# Sheet1.net
KiCad netlist of a schematic drawn in Altium Designer
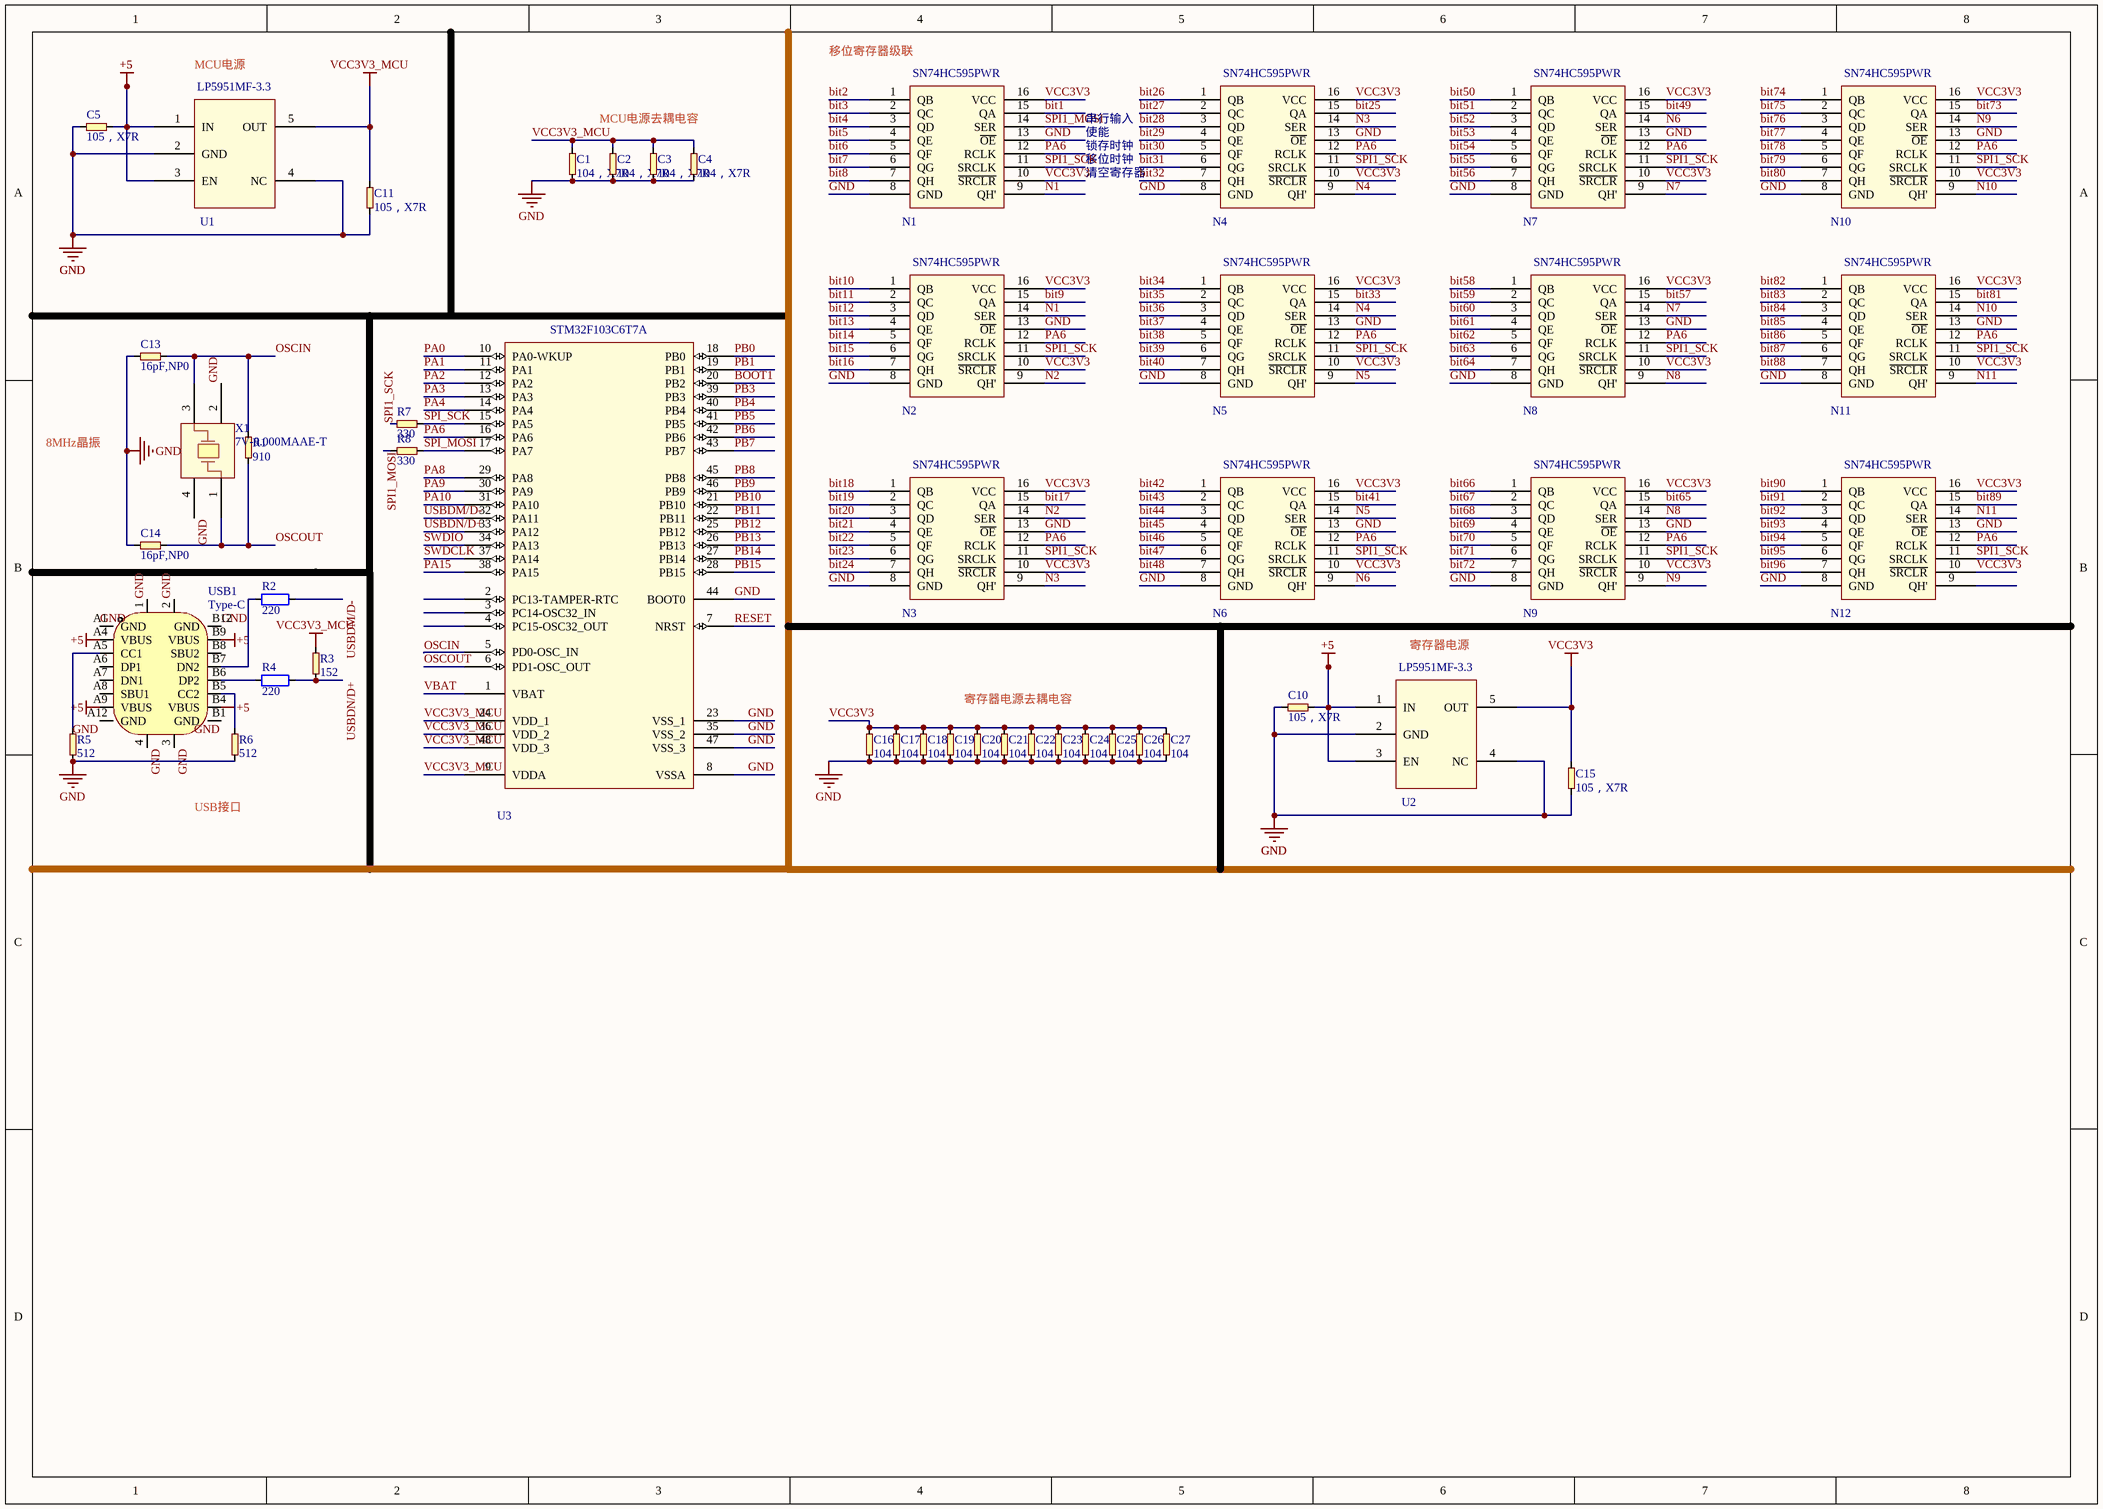
[diagram p0: Sheet1.SchDoc]

(export (version "E")
  (design (tool "Eeschema 10.0.6"))
  (components
    (comp (ref "C1") (value "104，X7R") (footprint "0603") (libsource (lib "原理图集成库") (part "0603电容")))
    (comp (ref "C2") (value "104，X7R") (footprint "0603") (libsource (lib "原理图集成库") (part "0603电容")))
    (comp (ref "C3") (value "104，X7R") (footprint "0603") (libsource (lib "原理图集成库") (part "0603电容")))
    (comp (ref "C4") (value "104，X7R") (footprint "0603") (libsource (lib "原理图集成库") (part "0603电容")))
    (comp (ref "C5") (value "105，X7R") (footprint "0603") (libsource (lib "") (part "0603电容_1")))
    (comp (ref "C10") (value "105，X7R") (footprint "0603") (libsource (lib "") (part "0603电容_1")))
    (comp (ref "C11") (value "105，X7R") (footprint "0603") (libsource (lib "原理图集成库") (part "0603电容")))
    (comp (ref "C13") (value "16pF,NP0") (footprint "0603") (libsource (lib "") (part "0603电容_1")))
    (comp (ref "C14") (value "16pF,NP0") (footprint "0603") (libsource (lib "") (part "0603电容_1")))
    (comp (ref "C15") (value "105，X7R") (footprint "0603") (libsource (lib "原理图集成库") (part "0603电容")))
    (comp (ref "C16") (value "104") (footprint "0603") (libsource (lib "原理图集成库") (part "0603电容")))
    (comp (ref "C17") (value "104") (footprint "0603") (libsource (lib "原理图集成库") (part "0603电容")))
    (comp (ref "C18") (value "104") (footprint "0603") (libsource (lib "原理图集成库") (part "0603电容")))
    (comp (ref "C19") (value "104") (footprint "0603") (libsource (lib "原理图集成库") (part "0603电容")))
    (comp (ref "C20") (value "104") (footprint "0603") (libsource (lib "原理图集成库") (part "0603电容")))
    (comp (ref "C21") (value "104") (footprint "0603") (libsource (lib "原理图集成库") (part "0603电容")))
    (comp (ref "C22") (value "104") (footprint "0603") (libsource (lib "原理图集成库") (part "0603电容")))
    (comp (ref "C23") (value "104") (footprint "0603") (libsource (lib "原理图集成库") (part "0603电容")))
    (comp (ref "C24") (value "104") (footprint "0603") (libsource (lib "原理图集成库") (part "0603电容")))
    (comp (ref "C25") (value "104") (footprint "0603") (libsource (lib "原理图集成库") (part "0603电容")))
    (comp (ref "C26") (value "104") (footprint "0603") (libsource (lib "原理图集成库") (part "0603电容")))
    (comp (ref "C27") (value "104") (footprint "0603") (libsource (lib "原理图集成库") (part "0603电容")))
    (comp (ref "N1")
      (value "SN74HC595PWR")
      (footprint "TSSOP16-0r65-5r0x4r4-H1r2:TSSOP16-0r65-5r0x4r4-H1r2")
      (libsource (lib "altium-import") (part "root_0_SN74HC595PWR_"))
    )
    (comp (ref "N2")
      (value "SN74HC595PWR")
      (footprint "TSSOP16-0r65-5r0x4r4-H1r2:TSSOP16-0r65-5r0x4r4-H1r2")
      (libsource (lib "altium-import") (part "root_0_SN74HC595PWR_"))
    )
    (comp (ref "N3")
      (value "SN74HC595PWR")
      (footprint "TSSOP16-0r65-5r0x4r4-H1r2:TSSOP16-0r65-5r0x4r4-H1r2")
      (libsource (lib "altium-import") (part "root_0_SN74HC595PWR_"))
    )
    (comp (ref "N4")
      (value "SN74HC595PWR")
      (footprint "TSSOP16-0r65-5r0x4r4-H1r2:TSSOP16-0r65-5r0x4r4-H1r2")
      (libsource (lib "altium-import") (part "root_0_SN74HC595PWR_"))
    )
    (comp (ref "N5")
      (value "SN74HC595PWR")
      (footprint "TSSOP16-0r65-5r0x4r4-H1r2:TSSOP16-0r65-5r0x4r4-H1r2")
      (libsource (lib "altium-import") (part "root_0_SN74HC595PWR_"))
    )
    (comp (ref "N6")
      (value "SN74HC595PWR")
      (footprint "TSSOP16-0r65-5r0x4r4-H1r2:TSSOP16-0r65-5r0x4r4-H1r2")
      (libsource (lib "altium-import") (part "root_0_SN74HC595PWR_"))
    )
    (comp (ref "N7")
      (value "SN74HC595PWR")
      (footprint "TSSOP16-0r65-5r0x4r4-H1r2:TSSOP16-0r65-5r0x4r4-H1r2")
      (libsource (lib "altium-import") (part "root_0_SN74HC595PWR_"))
    )
    (comp (ref "N8")
      (value "SN74HC595PWR")
      (footprint "TSSOP16-0r65-5r0x4r4-H1r2:TSSOP16-0r65-5r0x4r4-H1r2")
      (libsource (lib "altium-import") (part "root_0_SN74HC595PWR_"))
    )
    (comp (ref "N9")
      (value "SN74HC595PWR")
      (footprint "TSSOP16-0r65-5r0x4r4-H1r2:TSSOP16-0r65-5r0x4r4-H1r2")
      (libsource (lib "altium-import") (part "root_0_SN74HC595PWR_"))
    )
    (comp (ref "N10")
      (value "SN74HC595PWR")
      (footprint "TSSOP16-0r65-5r0x4r4-H1r2:TSSOP16-0r65-5r0x4r4-H1r2")
      (libsource (lib "altium-import") (part "root_0_SN74HC595PWR_"))
    )
    (comp (ref "N11")
      (value "SN74HC595PWR")
      (footprint "TSSOP16-0r65-5r0x4r4-H1r2:TSSOP16-0r65-5r0x4r4-H1r2")
      (libsource (lib "altium-import") (part "root_0_SN74HC595PWR_"))
    )
    (comp (ref "N12")
      (value "SN74HC595PWR")
      (footprint "TSSOP16-0r65-5r0x4r4-H1r2:TSSOP16-0r65-5r0x4r4-H1r2")
      (libsource (lib "altium-import") (part "root_0_SN74HC595PWR_"))
    )
    (comp (ref "R1") (value "910") (footprint "0603") (libsource (lib "") (part "0603电阻_1")))
    (comp (ref "R2")
      (value "220")
      (footprint "RES_0402")
      (description "Resistor_SMD")
      (libsource (lib "RC") (part "Resistor_SMD"))
    )
    (comp (ref "R3") (value "152") (footprint "0603") (libsource (lib "") (part "0603电阻_1")))
    (comp (ref "R4")
      (value "220")
      (footprint "RES_0402")
      (description "Resistor_SMD")
      (libsource (lib "RC") (part "Resistor_SMD"))
    )
    (comp (ref "R5") (value "512") (footprint "0603") (libsource (lib "") (part "0603电阻_1")))
    (comp (ref "R6") (value "512") (footprint "0603") (libsource (lib "") (part "0603电阻_1")))
    (comp (ref "R7") (value "330") (footprint "0603") (libsource (lib "原理图集成库") (part "0603电阻")))
    (comp (ref "R8") (value "330") (footprint "0603") (libsource (lib "原理图集成库") (part "0603电阻")))
    (comp (ref "U1")
      (value "LP5951MF-3.3")
      (footprint "SOT23-5_2r90x1r60-H1r18-P0r95_G:SOT23-5_2r90x1r60-H1r18-P0r95_G")
      (libsource (lib "altium-import") (part "root_0_LP5951MF-3.3_"))
    )
    (comp (ref "U2")
      (value "LP5951MF-3.3")
      (footprint "SOT23-5_2r90x1r60-H1r18-P0r95_G:SOT23-5_2r90x1r60-H1r18-P0r95_G")
      (libsource (lib "altium-import") (part "root_0_LP5951MF-3.3_"))
    )
    (comp (ref "U3")
      (value "STM32F103C6T7A")
      (footprint "LQFP48-0r5-7x7-H1r6:LQFP48-0r5-7x7-H1r6")
      (libsource (lib "altium-import") (part "root_0_STM32F103C6T7A_"))
    )
    (comp (ref "USB1")
      (value "Type-C")
      (footprint "TYPE-C_16P")
      (description "USB-Type-C_16P")
      (libsource (lib "Connector") (part "USB-Type-C"))
    )
    (comp (ref "X1")
      (value "7V-8.000MAAE-T")
      (footprint "RESO3225-4_3r20x2r50-H0r90-P2r10:RESO3225-4_3r20x2r50-H0r90-P2r10")
      (libsource (lib "altium-import") (part "root_1_7V-8.000MAAE-T_"))
    )
  )
  (nets
    (net (code "1") (name "+5") (class "Default")
      (node (ref "C10") (pin "2") (pinfunction "2_2") (pintype "passive"))
      (node (ref "C5") (pin "2") (pinfunction "2_2") (pintype "passive"))
      (node (ref "U1") (pin "1") (pinfunction "IN_1") (pintype "passive"))
      (node (ref "U1") (pin "3") (pinfunction "EN_3") (pintype "passive"))
      (node (ref "U2") (pin "1") (pinfunction "IN_1") (pintype "passive"))
      (node (ref "U2") (pin "3") (pinfunction "EN_3") (pintype "passive"))
      (node (ref "USB1") (pin "A4") (pinfunction "VBUS_A4") (pintype "passive"))
      (node (ref "USB1") (pin "A9") (pinfunction "VBUS_A9") (pintype "passive"))
      (node (ref "USB1") (pin "B4") (pinfunction "VBUS_B4") (pintype "passive"))
      (node (ref "USB1") (pin "B9") (pinfunction "VBUS_B9") (pintype "passive"))
    )
    (net (code "2") (name "/BOOT1") (class "Default")
      (node (ref "U3") (pin "20") (pinfunction "PB2_20") (pintype "bidirectional"))
    )
    (net (code "3") (name "/N1") (class "Default")
      (node (ref "N1") (pin "9") (pinfunction "QH'_9") (pintype "passive"))
      (node (ref "N2") (pin "14") (pinfunction "SER_14") (pintype "passive"))
    )
    (net (code "4") (name "/N2") (class "Default")
      (node (ref "N2") (pin "9") (pinfunction "QH'_9") (pintype "passive"))
      (node (ref "N3") (pin "14") (pinfunction "SER_14") (pintype "passive"))
    )
    (net (code "5") (name "/N3") (class "Default")
      (node (ref "N3") (pin "9") (pinfunction "QH'_9") (pintype "passive"))
      (node (ref "N4") (pin "14") (pinfunction "SER_14") (pintype "passive"))
    )
    (net (code "6") (name "/N4") (class "Default")
      (node (ref "N4") (pin "9") (pinfunction "QH'_9") (pintype "passive"))
      (node (ref "N5") (pin "14") (pinfunction "SER_14") (pintype "passive"))
    )
    (net (code "7") (name "/N5") (class "Default")
      (node (ref "N5") (pin "9") (pinfunction "QH'_9") (pintype "passive"))
      (node (ref "N6") (pin "14") (pinfunction "SER_14") (pintype "passive"))
    )
    (net (code "8") (name "/N6") (class "Default")
      (node (ref "N6") (pin "9") (pinfunction "QH'_9") (pintype "passive"))
      (node (ref "N7") (pin "14") (pinfunction "SER_14") (pintype "passive"))
    )
    (net (code "9") (name "/N7") (class "Default")
      (node (ref "N7") (pin "9") (pinfunction "QH'_9") (pintype "passive"))
      (node (ref "N8") (pin "14") (pinfunction "SER_14") (pintype "passive"))
    )
    (net (code "10") (name "/N8") (class "Default")
      (node (ref "N8") (pin "9") (pinfunction "QH'_9") (pintype "passive"))
      (node (ref "N9") (pin "14") (pinfunction "SER_14") (pintype "passive"))
    )
    (net (code "11") (name "/N9") (class "Default")
      (node (ref "N10") (pin "14") (pinfunction "SER_14") (pintype "passive"))
      (node (ref "N9") (pin "9") (pinfunction "QH'_9") (pintype "passive"))
    )
    (net (code "12") (name "/N10") (class "Default")
      (node (ref "N10") (pin "9") (pinfunction "QH'_9") (pintype "passive"))
      (node (ref "N11") (pin "14") (pinfunction "SER_14") (pintype "passive"))
    )
    (net (code "13") (name "/N11") (class "Default")
      (node (ref "N11") (pin "9") (pinfunction "QH'_9") (pintype "passive"))
      (node (ref "N12") (pin "14") (pinfunction "SER_14") (pintype "passive"))
    )
    (net (code "14") (name "/OSCIN") (class "Default")
      (node (ref "C13") (pin "2") (pinfunction "2_2") (pintype "passive"))
      (node (ref "R1") (pin "2") (pinfunction "2_2") (pintype "passive"))
      (node (ref "U3") (pin "5") (pinfunction "PD0-OSC_IN_5") (pintype "bidirectional"))
      (node (ref "X1") (pin "3") (pinfunction "3_3") (pintype "passive"))
    )
    (net (code "15") (name "/OSCOUT") (class "Default")
      (node (ref "C14") (pin "2") (pinfunction "2_2") (pintype "passive"))
      (node (ref "R1") (pin "1") (pinfunction "1_1") (pintype "passive"))
      (node (ref "U3") (pin "6") (pinfunction "PD1-OSC_OUT_6") (pintype "bidirectional"))
      (node (ref "X1") (pin "1") (pinfunction "1_1") (pintype "passive"))
    )
    (net (code "16") (name "/PA0") (class "Default")
      (node (ref "U3") (pin "10") (pinfunction "PA0-WKUP_10") (pintype "bidirectional"))
    )
    (net (code "17") (name "/PA1") (class "Default")
      (node (ref "U3") (pin "11") (pinfunction "PA1_11") (pintype "bidirectional"))
    )
    (net (code "18") (name "/PA2") (class "Default")
      (node (ref "U3") (pin "12") (pinfunction "PA2_12") (pintype "bidirectional"))
    )
    (net (code "19") (name "/PA3") (class "Default")
      (node (ref "U3") (pin "13") (pinfunction "PA3_13") (pintype "bidirectional"))
    )
    (net (code "20") (name "/PA4") (class "Default")
      (node (ref "U3") (pin "14") (pinfunction "PA4_14") (pintype "bidirectional"))
    )
    (net (code "21") (name "/PA6") (class "Default")
      (node (ref "N1") (pin "12") (pinfunction "RCLK_12") (pintype "passive"))
      (node (ref "N10") (pin "12") (pinfunction "RCLK_12") (pintype "passive"))
      (node (ref "N11") (pin "12") (pinfunction "RCLK_12") (pintype "passive"))
      (node (ref "N12") (pin "12") (pinfunction "RCLK_12") (pintype "passive"))
      (node (ref "N2") (pin "12") (pinfunction "RCLK_12") (pintype "passive"))
      (node (ref "N3") (pin "12") (pinfunction "RCLK_12") (pintype "passive"))
      (node (ref "N4") (pin "12") (pinfunction "RCLK_12") (pintype "passive"))
      (node (ref "N5") (pin "12") (pinfunction "RCLK_12") (pintype "passive"))
      (node (ref "N6") (pin "12") (pinfunction "RCLK_12") (pintype "passive"))
      (node (ref "N7") (pin "12") (pinfunction "RCLK_12") (pintype "passive"))
      (node (ref "N8") (pin "12") (pinfunction "RCLK_12") (pintype "passive"))
      (node (ref "N9") (pin "12") (pinfunction "RCLK_12") (pintype "passive"))
      (node (ref "U3") (pin "16") (pinfunction "PA6_16") (pintype "bidirectional"))
    )
    (net (code "22") (name "/PA8") (class "Default")
      (node (ref "U3") (pin "29") (pinfunction "PA8_29") (pintype "bidirectional"))
    )
    (net (code "23") (name "/PA9") (class "Default")
      (node (ref "U3") (pin "30") (pinfunction "PA9_30") (pintype "bidirectional"))
    )
    (net (code "24") (name "/PA10") (class "Default")
      (node (ref "U3") (pin "31") (pinfunction "PA10_31") (pintype "bidirectional"))
    )
    (net (code "25") (name "/PA15") (class "Default")
      (node (ref "U3") (pin "38") (pinfunction "PA15_38") (pintype "bidirectional"))
    )
    (net (code "26") (name "/PB0") (class "Default")
      (node (ref "U3") (pin "18") (pinfunction "PB0_18") (pintype "bidirectional"))
    )
    (net (code "27") (name "/PB1") (class "Default")
      (node (ref "U3") (pin "19") (pinfunction "PB1_19") (pintype "bidirectional"))
    )
    (net (code "28") (name "/PB3") (class "Default")
      (node (ref "U3") (pin "39") (pinfunction "PB3_39") (pintype "bidirectional"))
    )
    (net (code "29") (name "/PB4") (class "Default")
      (node (ref "U3") (pin "40") (pinfunction "PB4_40") (pintype "bidirectional"))
    )
    (net (code "30") (name "/PB5") (class "Default")
      (node (ref "U3") (pin "41") (pinfunction "PB5_41") (pintype "bidirectional"))
    )
    (net (code "31") (name "/PB6") (class "Default")
      (node (ref "U3") (pin "42") (pinfunction "PB6_42") (pintype "bidirectional"))
    )
    (net (code "32") (name "/PB7") (class "Default")
      (node (ref "U3") (pin "43") (pinfunction "PB7_43") (pintype "bidirectional"))
    )
    (net (code "33") (name "/PB8") (class "Default")
      (node (ref "U3") (pin "45") (pinfunction "PB8_45") (pintype "bidirectional"))
    )
    (net (code "34") (name "/PB9") (class "Default")
      (node (ref "U3") (pin "46") (pinfunction "PB9_46") (pintype "bidirectional"))
    )
    (net (code "35") (name "/PB10") (class "Default")
      (node (ref "U3") (pin "21") (pinfunction "PB10_21") (pintype "bidirectional"))
    )
    (net (code "36") (name "/PB11") (class "Default")
      (node (ref "U3") (pin "22") (pinfunction "PB11_22") (pintype "bidirectional"))
    )
    (net (code "37") (name "/PB12") (class "Default")
      (node (ref "U3") (pin "25") (pinfunction "PB12_25") (pintype "bidirectional"))
    )
    (net (code "38") (name "/PB13") (class "Default")
      (node (ref "U3") (pin "26") (pinfunction "PB13_26") (pintype "bidirectional"))
    )
    (net (code "39") (name "/PB14") (class "Default")
      (node (ref "U3") (pin "27") (pinfunction "PB14_27") (pintype "bidirectional"))
    )
    (net (code "40") (name "/PB15") (class "Default")
      (node (ref "U3") (pin "28") (pinfunction "PB15_28") (pintype "bidirectional"))
    )
    (net (code "41") (name "/RESET") (class "Default")
      (node (ref "U3") (pin "7") (pinfunction "NRST_7") (pintype "bidirectional"))
    )
    (net (code "42") (name "/SPI1_MOSI") (class "Default")
      (node (ref "N1") (pin "14") (pinfunction "SER_14") (pintype "passive"))
      (node (ref "R8") (pin "1") (pinfunction "1_1") (pintype "passive"))
    )
    (net (code "43") (name "/SPI1_SCK") (class "Default")
      (node (ref "N1") (pin "11") (pinfunction "SRCLK_11") (pintype "passive"))
      (node (ref "N10") (pin "11") (pinfunction "SRCLK_11") (pintype "passive"))
      (node (ref "N11") (pin "11") (pinfunction "SRCLK_11") (pintype "passive"))
      (node (ref "N12") (pin "11") (pinfunction "SRCLK_11") (pintype "passive"))
      (node (ref "N2") (pin "11") (pinfunction "SRCLK_11") (pintype "passive"))
      (node (ref "N3") (pin "11") (pinfunction "SRCLK_11") (pintype "passive"))
      (node (ref "N4") (pin "11") (pinfunction "SRCLK_11") (pintype "passive"))
      (node (ref "N5") (pin "11") (pinfunction "SRCLK_11") (pintype "passive"))
      (node (ref "N6") (pin "11") (pinfunction "SRCLK_11") (pintype "passive"))
      (node (ref "N7") (pin "11") (pinfunction "SRCLK_11") (pintype "passive"))
      (node (ref "N8") (pin "11") (pinfunction "SRCLK_11") (pintype "passive"))
      (node (ref "N9") (pin "11") (pinfunction "SRCLK_11") (pintype "passive"))
      (node (ref "R7") (pin "1") (pinfunction "1_1") (pintype "passive"))
    )
    (net (code "44") (name "/SPI_MOSI") (class "Default")
      (node (ref "R8") (pin "2") (pinfunction "2_2") (pintype "passive"))
      (node (ref "U3") (pin "17") (pinfunction "PA7_17") (pintype "bidirectional"))
    )
    (net (code "45") (name "/SPI_SCK") (class "Default")
      (node (ref "R7") (pin "2") (pinfunction "2_2") (pintype "passive"))
      (node (ref "U3") (pin "15") (pinfunction "PA5_15") (pintype "bidirectional"))
    )
    (net (code "46") (name "/SWDCLK") (class "Default")
      (node (ref "U3") (pin "37") (pinfunction "PA14_37") (pintype "bidirectional"))
    )
    (net (code "47") (name "/SWDIO") (class "Default")
      (node (ref "U3") (pin "34") (pinfunction "PA13_34") (pintype "bidirectional"))
    )
    (net (code "48") (name "/USBDM{slash}D-") (class "Default")
      (node (ref "R2") (pin "2") (pinfunction "2_2") (pintype "passive"))
      (node (ref "U3") (pin "32") (pinfunction "PA11_32") (pintype "bidirectional"))
    )
    (net (code "49") (name "/USBDN{slash}D+") (class "Default")
      (node (ref "R3") (pin "1") (pinfunction "1_1") (pintype "passive"))
      (node (ref "R4") (pin "2") (pinfunction "2_2") (pintype "passive"))
      (node (ref "U3") (pin "33") (pinfunction "PA12_33") (pintype "bidirectional"))
    )
    (net (code "50") (name "/VBAT") (class "Default")
      (node (ref "U3") (pin "1") (pinfunction "VBAT_1") (pintype "power_in"))
    )
    (net (code "51") (name "/bit1") (class "Default")
      (node (ref "N1") (pin "15") (pinfunction "QA_15") (pintype "passive"))
    )
    (net (code "52") (name "/bit2") (class "Default")
      (node (ref "N1") (pin "1") (pinfunction "QB_1") (pintype "passive"))
    )
    (net (code "53") (name "/bit3") (class "Default")
      (node (ref "N1") (pin "2") (pinfunction "QC_2") (pintype "passive"))
    )
    (net (code "54") (name "/bit4") (class "Default")
      (node (ref "N1") (pin "3") (pinfunction "QD_3") (pintype "passive"))
    )
    (net (code "55") (name "/bit5") (class "Default")
      (node (ref "N1") (pin "4") (pinfunction "QE_4") (pintype "passive"))
    )
    (net (code "56") (name "/bit6") (class "Default")
      (node (ref "N1") (pin "5") (pinfunction "QF_5") (pintype "passive"))
    )
    (net (code "57") (name "/bit7") (class "Default")
      (node (ref "N1") (pin "6") (pinfunction "QG_6") (pintype "passive"))
    )
    (net (code "58") (name "/bit8") (class "Default")
      (node (ref "N1") (pin "7") (pinfunction "QH_7") (pintype "passive"))
    )
    (net (code "59") (name "/bit9") (class "Default")
      (node (ref "N2") (pin "15") (pinfunction "QA_15") (pintype "passive"))
    )
    (net (code "60") (name "/bit10") (class "Default")
      (node (ref "N2") (pin "1") (pinfunction "QB_1") (pintype "passive"))
    )
    (net (code "61") (name "/bit11") (class "Default")
      (node (ref "N2") (pin "2") (pinfunction "QC_2") (pintype "passive"))
    )
    (net (code "62") (name "/bit12") (class "Default")
      (node (ref "N2") (pin "3") (pinfunction "QD_3") (pintype "passive"))
    )
    (net (code "63") (name "/bit13") (class "Default")
      (node (ref "N2") (pin "4") (pinfunction "QE_4") (pintype "passive"))
    )
    (net (code "64") (name "/bit14") (class "Default")
      (node (ref "N2") (pin "5") (pinfunction "QF_5") (pintype "passive"))
    )
    (net (code "65") (name "/bit15") (class "Default")
      (node (ref "N2") (pin "6") (pinfunction "QG_6") (pintype "passive"))
    )
    (net (code "66") (name "/bit16") (class "Default")
      (node (ref "N2") (pin "7") (pinfunction "QH_7") (pintype "passive"))
    )
    (net (code "67") (name "/bit17") (class "Default")
      (node (ref "N3") (pin "15") (pinfunction "QA_15") (pintype "passive"))
    )
    (net (code "68") (name "/bit18") (class "Default")
      (node (ref "N3") (pin "1") (pinfunction "QB_1") (pintype "passive"))
    )
    (net (code "69") (name "/bit19") (class "Default")
      (node (ref "N3") (pin "2") (pinfunction "QC_2") (pintype "passive"))
    )
    (net (code "70") (name "/bit20") (class "Default")
      (node (ref "N3") (pin "3") (pinfunction "QD_3") (pintype "passive"))
    )
    (net (code "71") (name "/bit21") (class "Default")
      (node (ref "N3") (pin "4") (pinfunction "QE_4") (pintype "passive"))
    )
    (net (code "72") (name "/bit22") (class "Default")
      (node (ref "N3") (pin "5") (pinfunction "QF_5") (pintype "passive"))
    )
    (net (code "73") (name "/bit23") (class "Default")
      (node (ref "N3") (pin "6") (pinfunction "QG_6") (pintype "passive"))
    )
    (net (code "74") (name "/bit24") (class "Default")
      (node (ref "N3") (pin "7") (pinfunction "QH_7") (pintype "passive"))
    )
    (net (code "75") (name "/bit25") (class "Default")
      (node (ref "N4") (pin "15") (pinfunction "QA_15") (pintype "passive"))
    )
    (net (code "76") (name "/bit26") (class "Default")
      (node (ref "N4") (pin "1") (pinfunction "QB_1") (pintype "passive"))
    )
    (net (code "77") (name "/bit27") (class "Default")
      (node (ref "N4") (pin "2") (pinfunction "QC_2") (pintype "passive"))
    )
    (net (code "78") (name "/bit28") (class "Default")
      (node (ref "N4") (pin "3") (pinfunction "QD_3") (pintype "passive"))
    )
    (net (code "79") (name "/bit29") (class "Default")
      (node (ref "N4") (pin "4") (pinfunction "QE_4") (pintype "passive"))
    )
    (net (code "80") (name "/bit30") (class "Default")
      (node (ref "N4") (pin "5") (pinfunction "QF_5") (pintype "passive"))
    )
    (net (code "81") (name "/bit31") (class "Default")
      (node (ref "N4") (pin "6") (pinfunction "QG_6") (pintype "passive"))
    )
    (net (code "82") (name "/bit32") (class "Default")
      (node (ref "N4") (pin "7") (pinfunction "QH_7") (pintype "passive"))
    )
    (net (code "83") (name "/bit33") (class "Default")
      (node (ref "N5") (pin "15") (pinfunction "QA_15") (pintype "passive"))
    )
    (net (code "84") (name "/bit34") (class "Default")
      (node (ref "N5") (pin "1") (pinfunction "QB_1") (pintype "passive"))
    )
    (net (code "85") (name "/bit35") (class "Default")
      (node (ref "N5") (pin "2") (pinfunction "QC_2") (pintype "passive"))
    )
    (net (code "86") (name "/bit36") (class "Default")
      (node (ref "N5") (pin "3") (pinfunction "QD_3") (pintype "passive"))
    )
    (net (code "87") (name "/bit37") (class "Default")
      (node (ref "N5") (pin "4") (pinfunction "QE_4") (pintype "passive"))
    )
    (net (code "88") (name "/bit38") (class "Default")
      (node (ref "N5") (pin "5") (pinfunction "QF_5") (pintype "passive"))
    )
    (net (code "89") (name "/bit39") (class "Default")
      (node (ref "N5") (pin "6") (pinfunction "QG_6") (pintype "passive"))
    )
    (net (code "90") (name "/bit40") (class "Default")
      (node (ref "N5") (pin "7") (pinfunction "QH_7") (pintype "passive"))
    )
    (net (code "91") (name "/bit41") (class "Default")
      (node (ref "N6") (pin "15") (pinfunction "QA_15") (pintype "passive"))
    )
    (net (code "92") (name "/bit42") (class "Default")
      (node (ref "N6") (pin "1") (pinfunction "QB_1") (pintype "passive"))
    )
    (net (code "93") (name "/bit43") (class "Default")
      (node (ref "N6") (pin "2") (pinfunction "QC_2") (pintype "passive"))
    )
    (net (code "94") (name "/bit44") (class "Default")
      (node (ref "N6") (pin "3") (pinfunction "QD_3") (pintype "passive"))
    )
    (net (code "95") (name "/bit45") (class "Default")
      (node (ref "N6") (pin "4") (pinfunction "QE_4") (pintype "passive"))
    )
    (net (code "96") (name "/bit46") (class "Default")
      (node (ref "N6") (pin "5") (pinfunction "QF_5") (pintype "passive"))
    )
    (net (code "97") (name "/bit47") (class "Default")
      (node (ref "N6") (pin "6") (pinfunction "QG_6") (pintype "passive"))
    )
    (net (code "98") (name "/bit48") (class "Default")
      (node (ref "N6") (pin "7") (pinfunction "QH_7") (pintype "passive"))
    )
    (net (code "99") (name "/bit49") (class "Default")
      (node (ref "N7") (pin "15") (pinfunction "QA_15") (pintype "passive"))
    )
    (net (code "100") (name "/bit50") (class "Default")
      (node (ref "N7") (pin "1") (pinfunction "QB_1") (pintype "passive"))
    )
    (net (code "101") (name "/bit51") (class "Default")
      (node (ref "N7") (pin "2") (pinfunction "QC_2") (pintype "passive"))
    )
    (net (code "102") (name "/bit52") (class "Default")
      (node (ref "N7") (pin "3") (pinfunction "QD_3") (pintype "passive"))
    )
    (net (code "103") (name "/bit53") (class "Default")
      (node (ref "N7") (pin "4") (pinfunction "QE_4") (pintype "passive"))
    )
    (net (code "104") (name "/bit54") (class "Default")
      (node (ref "N7") (pin "5") (pinfunction "QF_5") (pintype "passive"))
    )
    (net (code "105") (name "/bit55") (class "Default")
      (node (ref "N7") (pin "6") (pinfunction "QG_6") (pintype "passive"))
    )
    (net (code "106") (name "/bit56") (class "Default")
      (node (ref "N7") (pin "7") (pinfunction "QH_7") (pintype "passive"))
    )
    (net (code "107") (name "/bit57") (class "Default")
      (node (ref "N8") (pin "15") (pinfunction "QA_15") (pintype "passive"))
    )
    (net (code "108") (name "/bit58") (class "Default")
      (node (ref "N8") (pin "1") (pinfunction "QB_1") (pintype "passive"))
    )
    (net (code "109") (name "/bit59") (class "Default")
      (node (ref "N8") (pin "2") (pinfunction "QC_2") (pintype "passive"))
    )
    (net (code "110") (name "/bit60") (class "Default")
      (node (ref "N8") (pin "3") (pinfunction "QD_3") (pintype "passive"))
    )
    (net (code "111") (name "/bit61") (class "Default")
      (node (ref "N8") (pin "4") (pinfunction "QE_4") (pintype "passive"))
    )
    (net (code "112") (name "/bit62") (class "Default")
      (node (ref "N8") (pin "5") (pinfunction "QF_5") (pintype "passive"))
    )
    (net (code "113") (name "/bit63") (class "Default")
      (node (ref "N8") (pin "6") (pinfunction "QG_6") (pintype "passive"))
    )
    (net (code "114") (name "/bit64") (class "Default")
      (node (ref "N8") (pin "7") (pinfunction "QH_7") (pintype "passive"))
    )
    (net (code "115") (name "/bit65") (class "Default")
      (node (ref "N9") (pin "15") (pinfunction "QA_15") (pintype "passive"))
    )
    (net (code "116") (name "/bit66") (class "Default")
      (node (ref "N9") (pin "1") (pinfunction "QB_1") (pintype "passive"))
    )
    (net (code "117") (name "/bit67") (class "Default")
      (node (ref "N9") (pin "2") (pinfunction "QC_2") (pintype "passive"))
    )
    (net (code "118") (name "/bit68") (class "Default")
      (node (ref "N9") (pin "3") (pinfunction "QD_3") (pintype "passive"))
    )
    (net (code "119") (name "/bit69") (class "Default")
      (node (ref "N9") (pin "4") (pinfunction "QE_4") (pintype "passive"))
    )
    (net (code "120") (name "/bit70") (class "Default")
      (node (ref "N9") (pin "5") (pinfunction "QF_5") (pintype "passive"))
    )
    (net (code "121") (name "/bit71") (class "Default")
      (node (ref "N9") (pin "6") (pinfunction "QG_6") (pintype "passive"))
    )
    (net (code "122") (name "/bit72") (class "Default")
      (node (ref "N9") (pin "7") (pinfunction "QH_7") (pintype "passive"))
    )
    (net (code "123") (name "/bit73") (class "Default")
      (node (ref "N10") (pin "15") (pinfunction "QA_15") (pintype "passive"))
    )
    (net (code "124") (name "/bit74") (class "Default")
      (node (ref "N10") (pin "1") (pinfunction "QB_1") (pintype "passive"))
    )
    (net (code "125") (name "/bit75") (class "Default")
      (node (ref "N10") (pin "2") (pinfunction "QC_2") (pintype "passive"))
    )
    (net (code "126") (name "/bit76") (class "Default")
      (node (ref "N10") (pin "3") (pinfunction "QD_3") (pintype "passive"))
    )
    (net (code "127") (name "/bit77") (class "Default")
      (node (ref "N10") (pin "4") (pinfunction "QE_4") (pintype "passive"))
    )
    (net (code "128") (name "/bit78") (class "Default")
      (node (ref "N10") (pin "5") (pinfunction "QF_5") (pintype "passive"))
    )
    (net (code "129") (name "/bit79") (class "Default")
      (node (ref "N10") (pin "6") (pinfunction "QG_6") (pintype "passive"))
    )
    (net (code "130") (name "/bit80") (class "Default")
      (node (ref "N10") (pin "7") (pinfunction "QH_7") (pintype "passive"))
    )
    (net (code "131") (name "/bit81") (class "Default")
      (node (ref "N11") (pin "15") (pinfunction "QA_15") (pintype "passive"))
    )
    (net (code "132") (name "/bit82") (class "Default")
      (node (ref "N11") (pin "1") (pinfunction "QB_1") (pintype "passive"))
    )
    (net (code "133") (name "/bit83") (class "Default")
      (node (ref "N11") (pin "2") (pinfunction "QC_2") (pintype "passive"))
    )
    (net (code "134") (name "/bit84") (class "Default")
      (node (ref "N11") (pin "3") (pinfunction "QD_3") (pintype "passive"))
    )
    (net (code "135") (name "/bit85") (class "Default")
      (node (ref "N11") (pin "4") (pinfunction "QE_4") (pintype "passive"))
    )
    (net (code "136") (name "/bit86") (class "Default")
      (node (ref "N11") (pin "5") (pinfunction "QF_5") (pintype "passive"))
    )
    (net (code "137") (name "/bit87") (class "Default")
      (node (ref "N11") (pin "6") (pinfunction "QG_6") (pintype "passive"))
    )
    (net (code "138") (name "/bit88") (class "Default")
      (node (ref "N11") (pin "7") (pinfunction "QH_7") (pintype "passive"))
    )
    (net (code "139") (name "/bit89") (class "Default")
      (node (ref "N12") (pin "15") (pinfunction "QA_15") (pintype "passive"))
    )
    (net (code "140") (name "/bit90") (class "Default")
      (node (ref "N12") (pin "1") (pinfunction "QB_1") (pintype "passive"))
    )
    (net (code "141") (name "/bit91") (class "Default")
      (node (ref "N12") (pin "2") (pinfunction "QC_2") (pintype "passive"))
    )
    (net (code "142") (name "/bit92") (class "Default")
      (node (ref "N12") (pin "3") (pinfunction "QD_3") (pintype "passive"))
    )
    (net (code "143") (name "/bit93") (class "Default")
      (node (ref "N12") (pin "4") (pinfunction "QE_4") (pintype "passive"))
    )
    (net (code "144") (name "/bit94") (class "Default")
      (node (ref "N12") (pin "5") (pinfunction "QF_5") (pintype "passive"))
    )
    (net (code "145") (name "/bit95") (class "Default")
      (node (ref "N12") (pin "6") (pinfunction "QG_6") (pintype "passive"))
    )
    (net (code "146") (name "/bit96") (class "Default")
      (node (ref "N12") (pin "7") (pinfunction "QH_7") (pintype "passive"))
    )
    (net (code "147") (name "GND") (class "Default")
      (node (ref "C1") (pin "1") (pinfunction "1_1") (pintype "passive"))
      (node (ref "C10") (pin "1") (pinfunction "1_1") (pintype "passive"))
      (node (ref "C11") (pin "1") (pinfunction "1_1") (pintype "passive"))
      (node (ref "C13") (pin "1") (pinfunction "1_1") (pintype "passive"))
      (node (ref "C14") (pin "1") (pinfunction "1_1") (pintype "passive"))
      (node (ref "C15") (pin "1") (pinfunction "1_1") (pintype "passive"))
      (node (ref "C16") (pin "1") (pinfunction "1_1") (pintype "passive"))
      (node (ref "C17") (pin "1") (pinfunction "1_1") (pintype "passive"))
      (node (ref "C18") (pin "1") (pinfunction "1_1") (pintype "passive"))
      (node (ref "C19") (pin "1") (pinfunction "1_1") (pintype "passive"))
      (node (ref "C2") (pin "1") (pinfunction "1_1") (pintype "passive"))
      (node (ref "C20") (pin "1") (pinfunction "1_1") (pintype "passive"))
      (node (ref "C21") (pin "1") (pinfunction "1_1") (pintype "passive"))
      (node (ref "C22") (pin "1") (pinfunction "1_1") (pintype "passive"))
      (node (ref "C23") (pin "1") (pinfunction "1_1") (pintype "passive"))
      (node (ref "C24") (pin "1") (pinfunction "1_1") (pintype "passive"))
      (node (ref "C25") (pin "1") (pinfunction "1_1") (pintype "passive"))
      (node (ref "C26") (pin "1") (pinfunction "1_1") (pintype "passive"))
      (node (ref "C27") (pin "1") (pinfunction "1_1") (pintype "passive"))
      (node (ref "C3") (pin "1") (pinfunction "1_1") (pintype "passive"))
      (node (ref "C4") (pin "1") (pinfunction "1_1") (pintype "passive"))
      (node (ref "C5") (pin "1") (pinfunction "1_1") (pintype "passive"))
      (node (ref "N1") (pin "13") (pinfunction "~{OE}_13") (pintype "passive"))
      (node (ref "N1") (pin "8") (pinfunction "GND_8") (pintype "passive"))
      (node (ref "N10") (pin "13") (pinfunction "~{OE}_13") (pintype "passive"))
      (node (ref "N10") (pin "8") (pinfunction "GND_8") (pintype "passive"))
      (node (ref "N11") (pin "13") (pinfunction "~{OE}_13") (pintype "passive"))
      (node (ref "N11") (pin "8") (pinfunction "GND_8") (pintype "passive"))
      (node (ref "N12") (pin "13") (pinfunction "~{OE}_13") (pintype "passive"))
      (node (ref "N12") (pin "8") (pinfunction "GND_8") (pintype "passive"))
      (node (ref "N2") (pin "13") (pinfunction "~{OE}_13") (pintype "passive"))
      (node (ref "N2") (pin "8") (pinfunction "GND_8") (pintype "passive"))
      (node (ref "N3") (pin "13") (pinfunction "~{OE}_13") (pintype "passive"))
      (node (ref "N3") (pin "8") (pinfunction "GND_8") (pintype "passive"))
      (node (ref "N4") (pin "13") (pinfunction "~{OE}_13") (pintype "passive"))
      (node (ref "N4") (pin "8") (pinfunction "GND_8") (pintype "passive"))
      (node (ref "N5") (pin "13") (pinfunction "~{OE}_13") (pintype "passive"))
      (node (ref "N5") (pin "8") (pinfunction "GND_8") (pintype "passive"))
      (node (ref "N6") (pin "13") (pinfunction "~{OE}_13") (pintype "passive"))
      (node (ref "N6") (pin "8") (pinfunction "GND_8") (pintype "passive"))
      (node (ref "N7") (pin "13") (pinfunction "~{OE}_13") (pintype "passive"))
      (node (ref "N7") (pin "8") (pinfunction "GND_8") (pintype "passive"))
      (node (ref "N8") (pin "13") (pinfunction "~{OE}_13") (pintype "passive"))
      (node (ref "N8") (pin "8") (pinfunction "GND_8") (pintype "passive"))
      (node (ref "N9") (pin "13") (pinfunction "~{OE}_13") (pintype "passive"))
      (node (ref "N9") (pin "8") (pinfunction "GND_8") (pintype "passive"))
      (node (ref "R5") (pin "1") (pinfunction "1_1") (pintype "passive"))
      (node (ref "R6") (pin "1") (pinfunction "1_1") (pintype "passive"))
      (node (ref "U1") (pin "2") (pinfunction "GND_2") (pintype "passive"))
      (node (ref "U1") (pin "4") (pinfunction "NC_4") (pintype "passive"))
      (node (ref "U2") (pin "2") (pinfunction "GND_2") (pintype "passive"))
      (node (ref "U2") (pin "4") (pinfunction "NC_4") (pintype "passive"))
      (node (ref "U3") (pin "23") (pinfunction "VSS_1_23") (pintype "power_in"))
      (node (ref "U3") (pin "35") (pinfunction "VSS_2_35") (pintype "power_in"))
      (node (ref "U3") (pin "44") (pinfunction "BOOT0_44") (pintype "passive"))
      (node (ref "U3") (pin "47") (pinfunction "VSS_3_47") (pintype "power_in"))
      (node (ref "U3") (pin "8") (pinfunction "VSSA_8") (pintype "power_in"))
      (node (ref "USB1") (pin "1") (pinfunction "2_1") (pintype "passive"))
      (node (ref "USB1") (pin "2") (pinfunction "2_2") (pintype "passive"))
      (node (ref "USB1") (pin "3") (pinfunction "3_3") (pintype "passive"))
      (node (ref "USB1") (pin "4") (pinfunction "4_4") (pintype "passive"))
      (node (ref "USB1") (pin "A1") (pinfunction "GND_A1") (pintype "passive"))
      (node (ref "USB1") (pin "A12") (pinfunction "GND_A12") (pintype "passive"))
      (node (ref "USB1") (pin "B1") (pinfunction "GND_B1") (pintype "passive"))
      (node (ref "USB1") (pin "B12") (pinfunction "GND_B12") (pintype "passive"))
      (node (ref "X1") (pin "2") (pinfunction "NC_2") (pintype "passive"))
      (node (ref "X1") (pin "4") (pinfunction "NC_4") (pintype "passive"))
    )
    (net (code "148") (name "Net-(USB1-CC1)") (class "Default")
      (node (ref "R5") (pin "2") (pinfunction "2_2") (pintype "passive"))
      (node (ref "USB1") (pin "A5") (pinfunction "CC1_A5") (pintype "passive"))
    )
    (net (code "149") (name "Net-(USB1-CC2)") (class "Default")
      (node (ref "R6") (pin "2") (pinfunction "2_2") (pintype "passive"))
      (node (ref "USB1") (pin "B5") (pinfunction "CC2_B5") (pintype "passive"))
    )
    (net (code "150") (name "Net-(USB1-DN2)") (class "Default")
      (node (ref "R2") (pin "1") (pinfunction "1_1") (pintype "passive"))
      (node (ref "USB1") (pin "B7") (pinfunction "DN2_B7") (pintype "passive"))
    )
    (net (code "151") (name "Net-(USB1-DP2)") (class "Default")
      (node (ref "R4") (pin "1") (pinfunction "1_1") (pintype "passive"))
      (node (ref "USB1") (pin "B6") (pinfunction "DP2_B6") (pintype "passive"))
    )
    (net (code "152") (name "VCC3V3") (class "Default")
      (node (ref "C15") (pin "2") (pinfunction "2_2") (pintype "passive"))
      (node (ref "C16") (pin "2") (pinfunction "2_2") (pintype "passive"))
      (node (ref "C17") (pin "2") (pinfunction "2_2") (pintype "passive"))
      (node (ref "C18") (pin "2") (pinfunction "2_2") (pintype "passive"))
      (node (ref "C19") (pin "2") (pinfunction "2_2") (pintype "passive"))
      (node (ref "C20") (pin "2") (pinfunction "2_2") (pintype "passive"))
      (node (ref "C21") (pin "2") (pinfunction "2_2") (pintype "passive"))
      (node (ref "C22") (pin "2") (pinfunction "2_2") (pintype "passive"))
      (node (ref "C23") (pin "2") (pinfunction "2_2") (pintype "passive"))
      (node (ref "C24") (pin "2") (pinfunction "2_2") (pintype "passive"))
      (node (ref "C25") (pin "2") (pinfunction "2_2") (pintype "passive"))
      (node (ref "C26") (pin "2") (pinfunction "2_2") (pintype "passive"))
      (node (ref "C27") (pin "2") (pinfunction "2_2") (pintype "passive"))
      (node (ref "N1") (pin "10") (pinfunction "~{SRCLR}_10") (pintype "passive"))
      (node (ref "N1") (pin "16") (pinfunction "VCC_16") (pintype "passive"))
      (node (ref "N10") (pin "10") (pinfunction "~{SRCLR}_10") (pintype "passive"))
      (node (ref "N10") (pin "16") (pinfunction "VCC_16") (pintype "passive"))
      (node (ref "N11") (pin "10") (pinfunction "~{SRCLR}_10") (pintype "passive"))
      (node (ref "N11") (pin "16") (pinfunction "VCC_16") (pintype "passive"))
      (node (ref "N12") (pin "10") (pinfunction "~{SRCLR}_10") (pintype "passive"))
      (node (ref "N12") (pin "16") (pinfunction "VCC_16") (pintype "passive"))
      (node (ref "N2") (pin "10") (pinfunction "~{SRCLR}_10") (pintype "passive"))
      (node (ref "N2") (pin "16") (pinfunction "VCC_16") (pintype "passive"))
      (node (ref "N3") (pin "10") (pinfunction "~{SRCLR}_10") (pintype "passive"))
      (node (ref "N3") (pin "16") (pinfunction "VCC_16") (pintype "passive"))
      (node (ref "N4") (pin "10") (pinfunction "~{SRCLR}_10") (pintype "passive"))
      (node (ref "N4") (pin "16") (pinfunction "VCC_16") (pintype "passive"))
      (node (ref "N5") (pin "10") (pinfunction "~{SRCLR}_10") (pintype "passive"))
      (node (ref "N5") (pin "16") (pinfunction "VCC_16") (pintype "passive"))
      (node (ref "N6") (pin "10") (pinfunction "~{SRCLR}_10") (pintype "passive"))
      (node (ref "N6") (pin "16") (pinfunction "VCC_16") (pintype "passive"))
      (node (ref "N7") (pin "10") (pinfunction "~{SRCLR}_10") (pintype "passive"))
      (node (ref "N7") (pin "16") (pinfunction "VCC_16") (pintype "passive"))
      (node (ref "N8") (pin "10") (pinfunction "~{SRCLR}_10") (pintype "passive"))
      (node (ref "N8") (pin "16") (pinfunction "VCC_16") (pintype "passive"))
      (node (ref "N9") (pin "10") (pinfunction "~{SRCLR}_10") (pintype "passive"))
      (node (ref "N9") (pin "16") (pinfunction "VCC_16") (pintype "passive"))
      (node (ref "U2") (pin "5") (pinfunction "OUT_5") (pintype "passive"))
    )
    (net (code "153") (name "VCC3V3_MCU") (class "Default")
      (node (ref "C1") (pin "2") (pinfunction "2_2") (pintype "passive"))
      (node (ref "C11") (pin "2") (pinfunction "2_2") (pintype "passive"))
      (node (ref "C2") (pin "2") (pinfunction "2_2") (pintype "passive"))
      (node (ref "C3") (pin "2") (pinfunction "2_2") (pintype "passive"))
      (node (ref "C4") (pin "2") (pinfunction "2_2") (pintype "passive"))
      (node (ref "R3") (pin "2") (pinfunction "2_2") (pintype "passive"))
      (node (ref "U1") (pin "5") (pinfunction "OUT_5") (pintype "passive"))
      (node (ref "U3") (pin "24") (pinfunction "VDD_1_24") (pintype "power_in"))
      (node (ref "U3") (pin "36") (pinfunction "VDD_2_36") (pintype "power_in"))
      (node (ref "U3") (pin "48") (pinfunction "VDD_3_48") (pintype "power_in"))
      (node (ref "U3") (pin "9") (pinfunction "VDDA_9") (pintype "power_in"))
    )
    (net (code "154") (name "unconnected-(N12-QH'-Pad9)") (class "Default")
      (node (ref "N12") (pin "9") (pinfunction "QH'_9") (pintype "passive"))
    )
    (net (code "155") (name "unconnected-(U3-PC13-TAMPER-RTC-Pad2)") (class "Default")
      (node (ref "U3") (pin "2") (pinfunction "PC13-TAMPER-RTC_2") (pintype "bidirectional"))
    )
    (net (code "156") (name "unconnected-(U3-PC14-OSC32_IN-Pad3)") (class "Default")
      (node (ref "U3") (pin "3") (pinfunction "PC14-OSC32_IN_3") (pintype "bidirectional"))
    )
    (net (code "157") (name "unconnected-(U3-PC15-OSC32_OUT-Pad4)") (class "Default")
      (node (ref "U3") (pin "4") (pinfunction "PC15-OSC32_OUT_4") (pintype "bidirectional"))
    )
    (net (code "158") (name "unconnected-(USB1-DN1-PadA7)") (class "Default")
      (node (ref "USB1") (pin "A7") (pinfunction "DN1_A7") (pintype "passive"))
    )
    (net (code "159") (name "unconnected-(USB1-DP1-PadA6)") (class "Default")
      (node (ref "USB1") (pin "A6") (pinfunction "DP1_A6") (pintype "passive"))
    )
    (net (code "160") (name "unconnected-(USB1-SBU1-PadA8)") (class "Default")
      (node (ref "USB1") (pin "A8") (pinfunction "SBU1_A8") (pintype "passive"))
    )
    (net (code "161") (name "unconnected-(USB1-SBU2-PadB8)") (class "Default")
      (node (ref "USB1") (pin "B8") (pinfunction "SBU2_B8") (pintype "passive"))
    )
  )
)
